# LB_BIT_w11_wirelessReceiver_v03_3_3_OHW.net
KiCad netlist of a schematic drawn in EAGLE
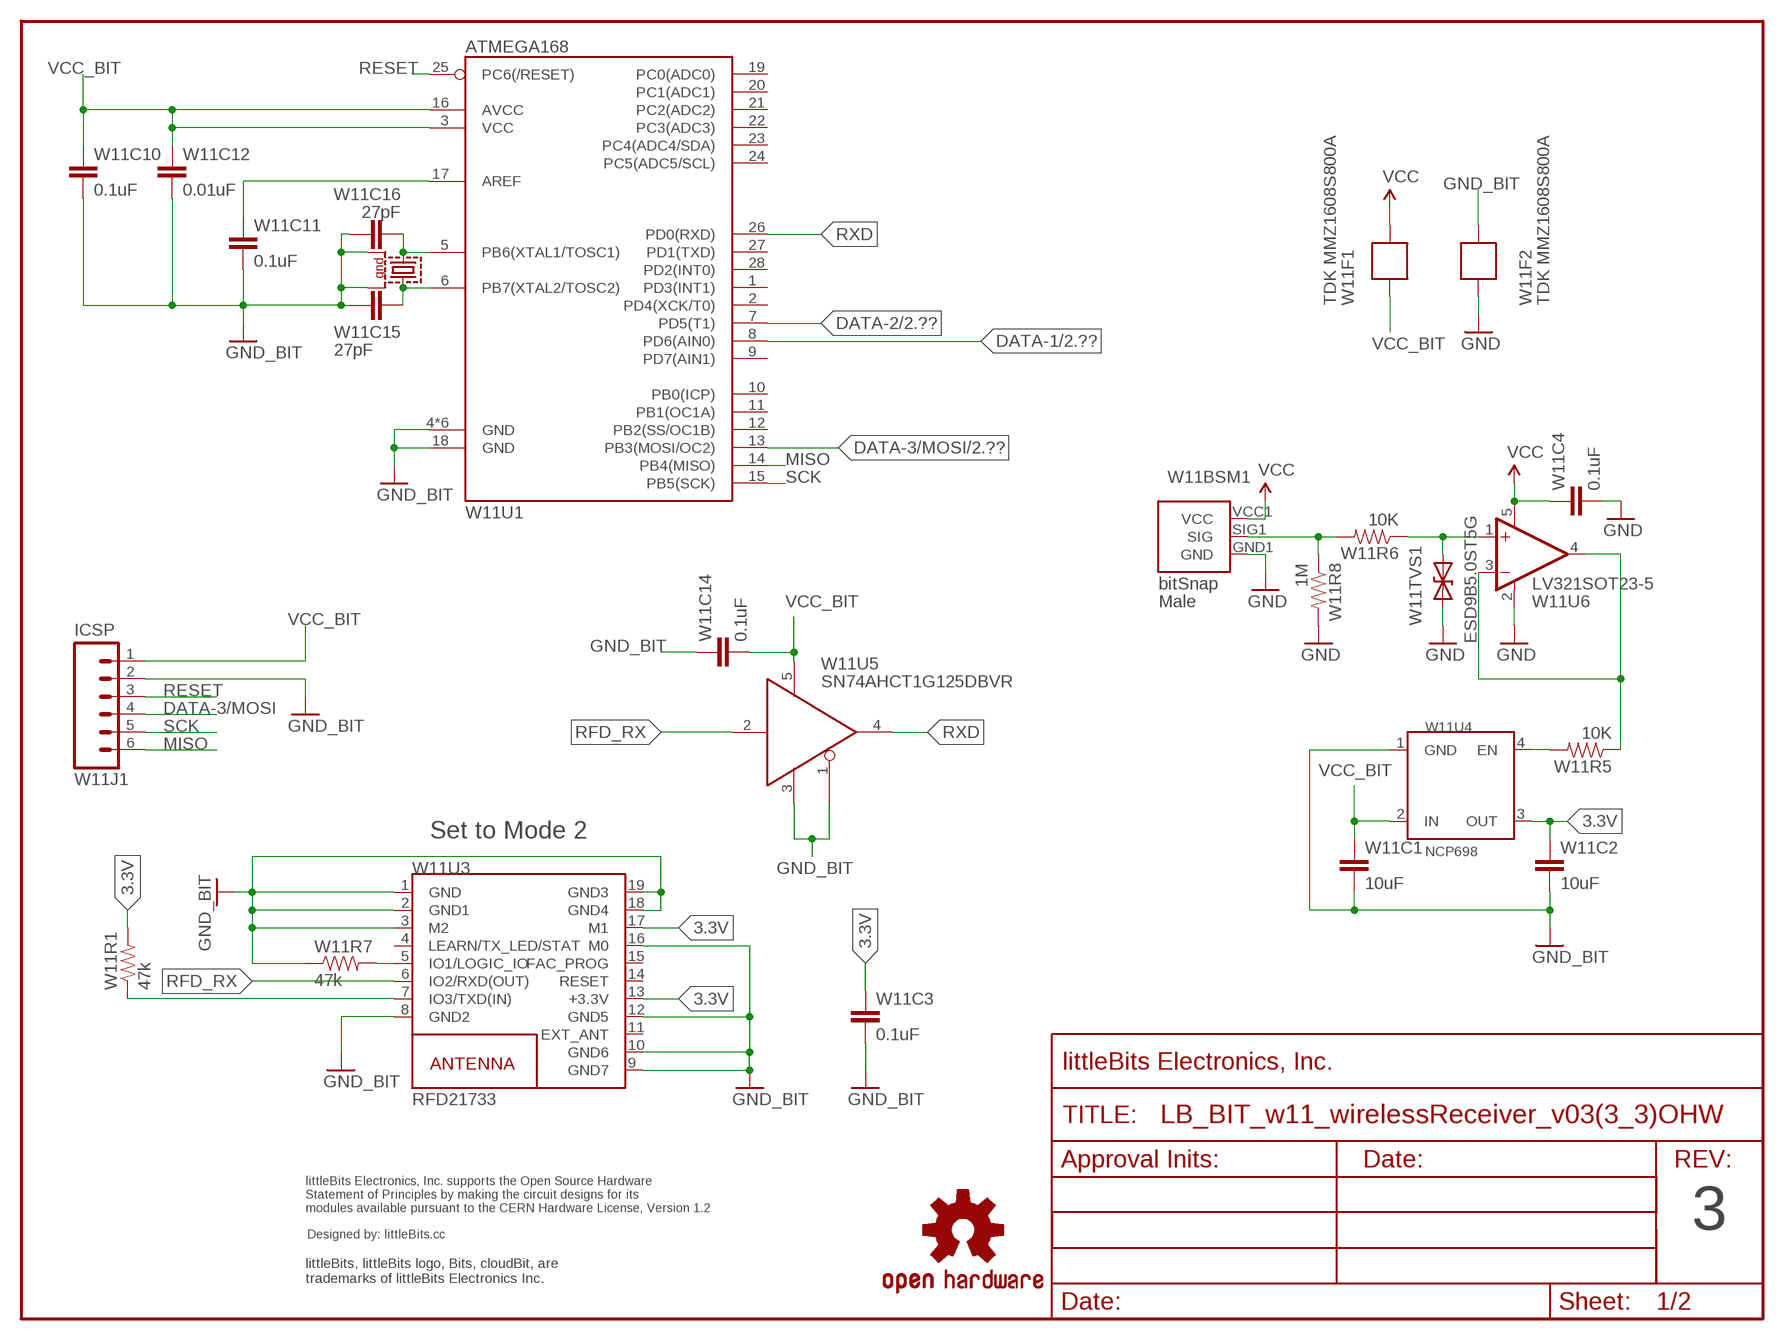
[diagram p0: schematic, sheet 1]
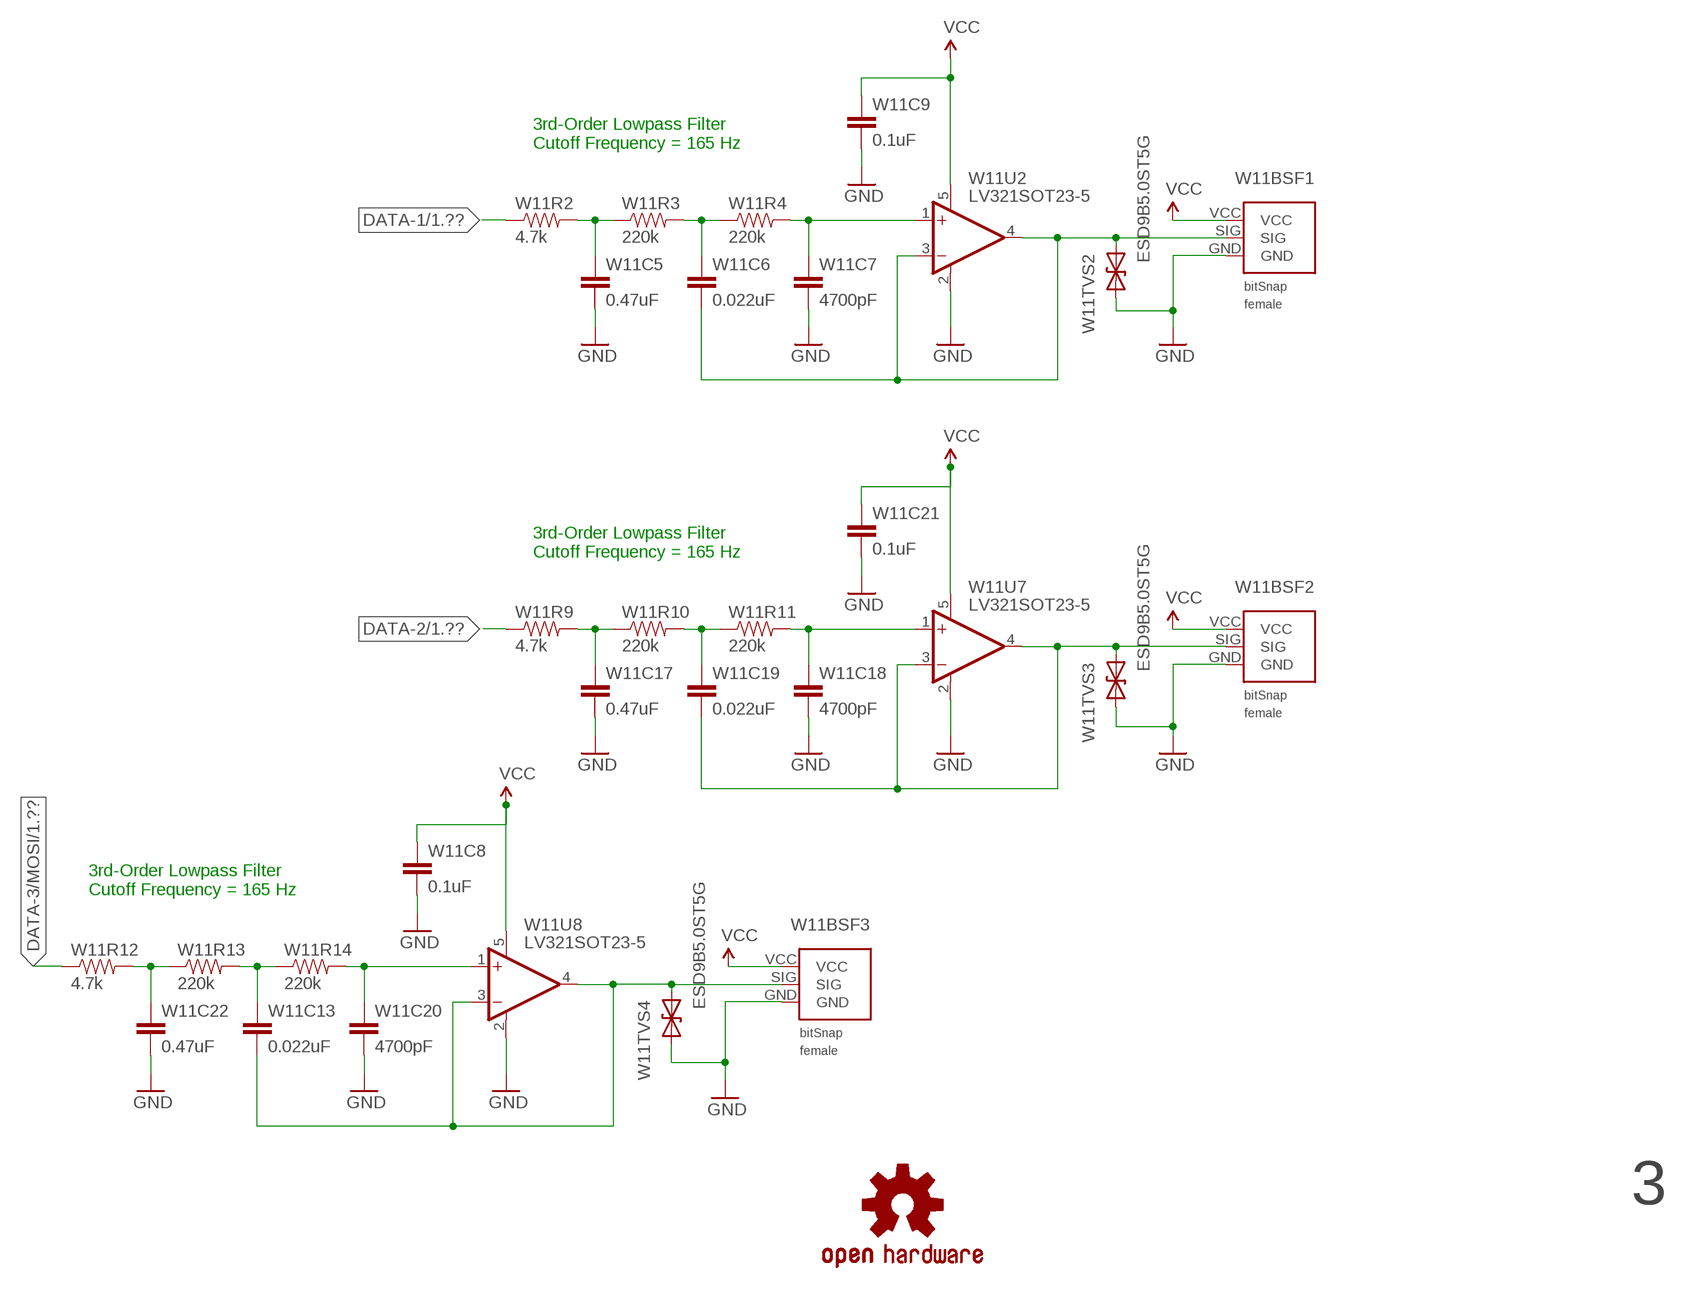
[diagram p1: schematic, sheet 2]

(export (version "E")
  (design (tool "Eeschema 10.0.6"))
  (components
    (comp (ref "FRAME1")
      (value "FRAME-LETTER-OHWOHW")
      (footprint "eagle-import:FABDWG01-OHW")
      (libsource (lib "eagle-import") (part "FRAME-LETTER-OHWOHW"))
    )
    (comp (ref "U$3")
      (value "OSHW-LOGOL")
      (footprint "eagle-import:OSHW-LOGO-L")
      (libsource (lib "eagle-import") (part "OSHW-LOGOL"))
    )
    (comp (ref "U$7")
      (value "OSHWCREDIT")
      (footprint "eagle-import:OSHWCREDIT")
      (libsource (lib "eagle-import") (part "OSHWCREDIT"))
    )
    (comp (ref "W11BSM1")
      (value "BITSNAP_V03_MALE")
      (footprint "eagle-import:BITSNAP_V03_MALE")
      (libsource (lib "eagle-import") (part "BITSNAP_V03_MALE"))
    )
    (comp (ref "W11C1")
      (value "10uF")
      (footprint "eagle-import:CAP-0603")
      (libsource (lib "eagle-import") (part "CAPCAP-0603"))
    )
    (comp (ref "W11C2")
      (value "10uF")
      (footprint "eagle-import:CAP-0603")
      (libsource (lib "eagle-import") (part "CAPCAP-0603"))
    )
    (comp (ref "W11C3")
      (value "0.1uF")
      (footprint "eagle-import:CAP-0603")
      (libsource (lib "eagle-import") (part "CAPCAP-0603"))
    )
    (comp (ref "W11C4")
      (value "0.1uF")
      (footprint "eagle-import:CAP-0603")
      (libsource (lib "eagle-import") (part "CAPCAP-0603"))
    )
    (comp (ref "W11C10")
      (value "0.1uF")
      (footprint "eagle-import:CAP-0603")
      (libsource (lib "eagle-import") (part "CAPCAP-0603"))
    )
    (comp (ref "W11C11")
      (value "0.1uF")
      (footprint "eagle-import:CAP-0603")
      (libsource (lib "eagle-import") (part "CAPCAP-0603"))
    )
    (comp (ref "W11C12")
      (value "0.01uF")
      (footprint "eagle-import:CAP-0603")
      (libsource (lib "eagle-import") (part "CAPCAP-0603"))
    )
    (comp (ref "W11C14")
      (value "0.1uF")
      (footprint "eagle-import:CAP-0603")
      (libsource (lib "eagle-import") (part "CAPCAP-0603"))
    )
    (comp (ref "W11C15")
      (value "27pF")
      (footprint "eagle-import:CAP-0603")
      (libsource (lib "eagle-import") (part "CAPCAP-0603"))
    )
    (comp (ref "W11C16")
      (value "27pF")
      (footprint "eagle-import:CAP-0603")
      (libsource (lib "eagle-import") (part "CAPCAP-0603"))
    )
    (comp (ref "W11F1")
      (value "TDK MMZ1608S800A")
      (footprint "eagle-import:R0603")
      (libsource (lib "eagle-import") (part "FERRITE-BEAD"))
    )
    (comp (ref "W11F2")
      (value "TDK MMZ1608S800A")
      (footprint "eagle-import:R0603")
      (libsource (lib "eagle-import") (part "FERRITE-BEAD"))
    )
    (comp (ref "W11J1")
      (value "ICSP")
      (footprint "eagle-import:SIP6-SM-0.1IN-NOS.S.")
      (libsource (lib "eagle-import") (part "HRD-60.1INCH_NO_SILKSCREEN"))
    )
    (comp (ref "W11R1")
      (value "47k")
      (footprint "eagle-import:RES-0603")
      (libsource (lib "eagle-import") (part "RESISTOR0603"))
    )
    (comp (ref "W11R5")
      (value "10K")
      (footprint "eagle-import:RES-0603")
      (libsource (lib "eagle-import") (part "RESISTOR0603"))
    )
    (comp (ref "W11R6")
      (value "10K")
      (footprint "eagle-import:RES-0603")
      (libsource (lib "eagle-import") (part "RESISTOR0603"))
    )
    (comp (ref "W11R7")
      (value "47k")
      (footprint "eagle-import:RES-0603")
      (libsource (lib "eagle-import") (part "RESISTOR0603"))
    )
    (comp (ref "W11R8")
      (value "1M")
      (footprint "eagle-import:RES-0603")
      (libsource (lib "eagle-import") (part "RESISTOR0603"))
    )
    (comp (ref "W11TVS1")
      (value "ESD9B5.0ST5G")
      (footprint "eagle-import:SOD-923")
      (libsource (lib "eagle-import") (part "DIODE-TVSSOD-923"))
    )
    (comp (ref "W11U1")
      (value "ATMEGA168")
      (footprint "eagle-import:VQFN28")
      (libsource (lib "eagle-import") (part "ATMEGA168-28PINVFQFN-28"))
    )
    (comp (ref "W11U3")
      (value "RFD21733")
      (footprint "eagle-import:RFD21733")
      (libsource (lib "eagle-import") (part "RFD_CHIP"))
    )
    (comp (ref "W11U4")
      (value "NCP698")
      (footprint "eagle-import:NCP698_SC82-AB")
      (libsource (lib "eagle-import") (part "NCP698"))
    )
    (comp (ref "W11U5")
      (value "SN74AHCT1G125DBVR")
      (footprint "eagle-import:SOT23-5")
      (libsource (lib "eagle-import") (part "5V_TO_3.3V_LEVEL-SHIFTERSOT23-5"))
    )
    (comp (ref "W11U6")
      (value "LV321SOT23-5")
      (footprint "eagle-import:SOT23-5")
      (libsource (lib "eagle-import") (part "LV321SOT23-5"))
    )
    (comp (ref "W11X1")
      (value "7B-8.000MAAJ-T")
      (footprint "eagle-import:CRYSTAL-SMD-7B-SERIES-5X3.2MM")
      (fields (field (name "MFG") "TXC") (field (name "MPN") "7B SERIES"))
      (libsource (lib "eagle-import") (part "CRYSTAL-SMD-7B-SERIES-TXC"))
    )
    (comp (ref "U$9")
      (value "OSHW-LOGOL")
      (footprint "eagle-import:OSHW-LOGO-L")
      (libsource (lib "eagle-import") (part "OSHW-LOGOL"))
    )
    (comp (ref "W11BSF1")
      (value "BITSNAP_V03_FEMALE")
      (footprint "eagle-import:BITSNAP_V03_FEMALE")
      (libsource (lib "eagle-import") (part "BITSNAP_V03_FEMALE"))
    )
    (comp (ref "W11BSF2")
      (value "BITSNAP_V03_FEMALE")
      (footprint "eagle-import:BITSNAP_V03_FEMALE")
      (libsource (lib "eagle-import") (part "BITSNAP_V03_FEMALE"))
    )
    (comp (ref "W11BSF3")
      (value "BITSNAP_V03_FEMALE")
      (footprint "eagle-import:BITSNAP_V03_FEMALE")
      (libsource (lib "eagle-import") (part "BITSNAP_V03_FEMALE"))
    )
    (comp (ref "W11C5")
      (value "0.47uF")
      (footprint "eagle-import:CAP-0603")
      (libsource (lib "eagle-import") (part "CAPCAP-0603"))
    )
    (comp (ref "W11C6")
      (value "0.022uF")
      (footprint "eagle-import:CAP-0603")
      (libsource (lib "eagle-import") (part "CAPCAP-0603"))
    )
    (comp (ref "W11C7")
      (value "4700pF")
      (footprint "eagle-import:CAP-0603")
      (libsource (lib "eagle-import") (part "CAPCAP-0603"))
    )
    (comp (ref "W11C8")
      (value "0.1uF")
      (footprint "eagle-import:CAP-0603")
      (libsource (lib "eagle-import") (part "CAPCAP-0603"))
    )
    (comp (ref "W11C9")
      (value "0.1uF")
      (footprint "eagle-import:CAP-0603")
      (libsource (lib "eagle-import") (part "CAPCAP-0603"))
    )
    (comp (ref "W11C13")
      (value "0.022uF")
      (footprint "eagle-import:CAP-0603")
      (libsource (lib "eagle-import") (part "CAPCAP-0603"))
    )
    (comp (ref "W11C17")
      (value "0.47uF")
      (footprint "eagle-import:CAP-0603")
      (libsource (lib "eagle-import") (part "CAPCAP-0603"))
    )
    (comp (ref "W11C18")
      (value "4700pF")
      (footprint "eagle-import:CAP-0603")
      (libsource (lib "eagle-import") (part "CAPCAP-0603"))
    )
    (comp (ref "W11C19")
      (value "0.022uF")
      (footprint "eagle-import:CAP-0603")
      (libsource (lib "eagle-import") (part "CAPCAP-0603"))
    )
    (comp (ref "W11C20")
      (value "4700pF")
      (footprint "eagle-import:CAP-0603")
      (libsource (lib "eagle-import") (part "CAPCAP-0603"))
    )
    (comp (ref "W11C21")
      (value "0.1uF")
      (footprint "eagle-import:CAP-0603")
      (libsource (lib "eagle-import") (part "CAPCAP-0603"))
    )
    (comp (ref "W11C22")
      (value "0.47uF")
      (footprint "eagle-import:CAP-0603")
      (libsource (lib "eagle-import") (part "CAPCAP-0603"))
    )
    (comp (ref "W11R2")
      (value "4.7k")
      (footprint "eagle-import:RES-0603")
      (libsource (lib "eagle-import") (part "RESISTOR0603"))
    )
    (comp (ref "W11R3")
      (value "220k")
      (footprint "eagle-import:RES-0603")
      (libsource (lib "eagle-import") (part "RESISTOR0603"))
    )
    (comp (ref "W11R4")
      (value "220k")
      (footprint "eagle-import:RES-0603")
      (libsource (lib "eagle-import") (part "RESISTOR0603"))
    )
    (comp (ref "W11R9")
      (value "4.7k")
      (footprint "eagle-import:RES-0603")
      (libsource (lib "eagle-import") (part "RESISTOR0603"))
    )
    (comp (ref "W11R10")
      (value "220k")
      (footprint "eagle-import:RES-0603")
      (libsource (lib "eagle-import") (part "RESISTOR0603"))
    )
    (comp (ref "W11R11")
      (value "220k")
      (footprint "eagle-import:RES-0603")
      (libsource (lib "eagle-import") (part "RESISTOR0603"))
    )
    (comp (ref "W11R12")
      (value "4.7k")
      (footprint "eagle-import:RES-0603")
      (libsource (lib "eagle-import") (part "RESISTOR0603"))
    )
    (comp (ref "W11R13")
      (value "220k")
      (footprint "eagle-import:RES-0603")
      (libsource (lib "eagle-import") (part "RESISTOR0603"))
    )
    (comp (ref "W11R14")
      (value "220k")
      (footprint "eagle-import:RES-0603")
      (libsource (lib "eagle-import") (part "RESISTOR0603"))
    )
    (comp (ref "W11TVS2")
      (value "ESD9B5.0ST5G")
      (footprint "eagle-import:SOD-923")
      (libsource (lib "eagle-import") (part "DIODE-TVSSOD-923"))
    )
    (comp (ref "W11TVS3")
      (value "ESD9B5.0ST5G")
      (footprint "eagle-import:SOD-923")
      (libsource (lib "eagle-import") (part "DIODE-TVSSOD-923"))
    )
    (comp (ref "W11TVS4")
      (value "ESD9B5.0ST5G")
      (footprint "eagle-import:SOD-923")
      (libsource (lib "eagle-import") (part "DIODE-TVSSOD-923"))
    )
    (comp (ref "W11U2")
      (value "LV321SOT23-5")
      (footprint "eagle-import:SOT23-5")
      (libsource (lib "eagle-import") (part "LV321SOT23-5"))
    )
    (comp (ref "W11U7")
      (value "LV321SOT23-5")
      (footprint "eagle-import:SOT23-5")
      (libsource (lib "eagle-import") (part "LV321SOT23-5"))
    )
    (comp (ref "W11U8")
      (value "LV321SOT23-5")
      (footprint "eagle-import:SOT23-5")
      (libsource (lib "eagle-import") (part "LV321SOT23-5"))
    )
  )
  (nets
    (net (code "1") (name "3.3V") (class "Default")
      (node (ref "W11C2") (pin "1") (pinfunction "1_1") (pintype "passive"))
      (node (ref "W11C3") (pin "1") (pinfunction "1_1") (pintype "passive"))
      (node (ref "W11R1") (pin "2") (pinfunction "2_2") (pintype "passive"))
      (node (ref "W11U3") (pin "13") (pinfunction "+3.3V_13") (pintype "bidirectional"))
      (node (ref "W11U3") (pin "17") (pinfunction "M1_17") (pintype "bidirectional"))
      (node (ref "W11U4") (pin "3") (pinfunction "OUT_3") (pintype "bidirectional"))
    )
    (net (code "2") (name "DATA-1") (class "Default")
      (node (ref "W11R2") (pin "1") (pinfunction "1_1") (pintype "passive"))
      (node (ref "W11U1") (pin "8") (pinfunction "PD6(AIN0)_8") (pintype "bidirectional"))
    )
    (net (code "3") (name "DATA-2") (class "Default")
      (node (ref "W11R9") (pin "1") (pinfunction "1_1") (pintype "passive"))
      (node (ref "W11U1") (pin "7") (pinfunction "PD5(T1)_7") (pintype "bidirectional"))
    )
    (net (code "4") (name "DATA-3{slash}MOSI") (class "Default")
      (node (ref "W11J1") (pin "4") (pinfunction "4_4") (pintype "passive"))
      (node (ref "W11R12") (pin "1") (pinfunction "1_1") (pintype "passive"))
      (node (ref "W11U1") (pin "13") (pinfunction "PB3(MOSI/OC2)_13") (pintype "bidirectional"))
    )
    (net (code "5") (name "GND") (class "Default")
      (node (ref "W11BSF1") (pin "GND") (pinfunction "GND_GND") (pintype "bidirectional"))
      (node (ref "W11BSF2") (pin "GND") (pinfunction "GND_GND") (pintype "bidirectional"))
      (node (ref "W11BSF3") (pin "GND") (pinfunction "GND_GND") (pintype "bidirectional"))
      (node (ref "W11BSM1") (pin "GND1") (pinfunction "GND_GND1") (pintype "bidirectional"))
      (node (ref "W11C17") (pin "2") (pinfunction "2_2") (pintype "passive"))
      (node (ref "W11C18") (pin "2") (pinfunction "2_2") (pintype "passive"))
      (node (ref "W11C20") (pin "2") (pinfunction "2_2") (pintype "passive"))
      (node (ref "W11C21") (pin "2") (pinfunction "2_2") (pintype "passive"))
      (node (ref "W11C22") (pin "2") (pinfunction "2_2") (pintype "passive"))
      (node (ref "W11C4") (pin "2") (pinfunction "2_2") (pintype "passive"))
      (node (ref "W11C5") (pin "2") (pinfunction "2_2") (pintype "passive"))
      (node (ref "W11C7") (pin "2") (pinfunction "2_2") (pintype "passive"))
      (node (ref "W11C8") (pin "2") (pinfunction "2_2") (pintype "passive"))
      (node (ref "W11C9") (pin "2") (pinfunction "2_2") (pintype "passive"))
      (node (ref "W11F2") (pin "2") (pinfunction "P$2_2") (pintype "bidirectional"))
      (node (ref "W11R8") (pin "2") (pinfunction "2_2") (pintype "passive"))
      (node (ref "W11TVS1") (pin "1") (pinfunction "A_1") (pintype "passive"))
      (node (ref "W11TVS2") (pin "1") (pinfunction "A_1") (pintype "passive"))
      (node (ref "W11TVS3") (pin "1") (pinfunction "A_1") (pintype "passive"))
      (node (ref "W11TVS4") (pin "1") (pinfunction "A_1") (pintype "passive"))
      (node (ref "W11U2") (pin "2") (pinfunction "V-_2") (pintype "power_in"))
      (node (ref "W11U6") (pin "2") (pinfunction "V-_2") (pintype "power_in"))
      (node (ref "W11U7") (pin "2") (pinfunction "V-_2") (pintype "power_in"))
      (node (ref "W11U8") (pin "2") (pinfunction "V-_2") (pintype "power_in"))
    )
    (net (code "6") (name "GND_BIT") (class "Default")
      (node (ref "W11C1") (pin "2") (pinfunction "2_2") (pintype "passive"))
      (node (ref "W11C10") (pin "2") (pinfunction "2_2") (pintype "passive"))
      (node (ref "W11C11") (pin "2") (pinfunction "2_2") (pintype "passive"))
      (node (ref "W11C12") (pin "2") (pinfunction "2_2") (pintype "passive"))
      (node (ref "W11C14") (pin "1") (pinfunction "1_1") (pintype "passive"))
      (node (ref "W11C15") (pin "2") (pinfunction "2_2") (pintype "passive"))
      (node (ref "W11C16") (pin "1") (pinfunction "1_1") (pintype "passive"))
      (node (ref "W11C2") (pin "2") (pinfunction "2_2") (pintype "passive"))
      (node (ref "W11C3") (pin "2") (pinfunction "2_2") (pintype "passive"))
      (node (ref "W11F2") (pin "1") (pinfunction "P$1_1") (pintype "bidirectional"))
      (node (ref "W11J1") (pin "2") (pinfunction "2_2") (pintype "passive"))
      (node (ref "W11R7") (pin "1") (pinfunction "1_1") (pintype "passive"))
      (node (ref "W11U1") (pin "18") (pinfunction "GND_18") (pintype "bidirectional"))
      (node (ref "W11U1") (pin "4") (pinfunction "GND_4") (pintype "bidirectional"))
      (node (ref "W11U1") (pin "TH") (pinfunction "GND_TH") (pintype "bidirectional"))
      (node (ref "W11U1") (pin "TH@1") (pinfunction "GND_TH@1") (pintype "bidirectional"))
      (node (ref "W11U1") (pin "TH@2") (pinfunction "GND_TH@2") (pintype "bidirectional"))
      (node (ref "W11U1") (pin "TH@3") (pinfunction "GND_TH@3") (pintype "bidirectional"))
      (node (ref "W11U1") (pin "TH@4") (pinfunction "GND_TH@4") (pintype "bidirectional"))
      (node (ref "W11U3") (pin "1") (pinfunction "GND_1") (pintype "bidirectional"))
      (node (ref "W11U3") (pin "10") (pinfunction "GND6_10") (pintype "bidirectional"))
      (node (ref "W11U3") (pin "12") (pinfunction "GND5_12") (pintype "bidirectional"))
      (node (ref "W11U3") (pin "16") (pinfunction "M0_16") (pintype "bidirectional"))
      (node (ref "W11U3") (pin "18") (pinfunction "GND4_18") (pintype "bidirectional"))
      (node (ref "W11U3") (pin "19") (pinfunction "GND3_19") (pintype "bidirectional"))
      (node (ref "W11U3") (pin "2") (pinfunction "GND1_2") (pintype "bidirectional"))
      (node (ref "W11U3") (pin "3") (pinfunction "M2_3") (pintype "bidirectional"))
      (node (ref "W11U3") (pin "8") (pinfunction "GND2_8") (pintype "bidirectional"))
      (node (ref "W11U3") (pin "9") (pinfunction "GND7_9") (pintype "bidirectional"))
      (node (ref "W11U4") (pin "1") (pinfunction "GND_1") (pintype "bidirectional"))
      (node (ref "W11U5") (pin "1") (pinfunction "1_1") (pintype "bidirectional"))
      (node (ref "W11U5") (pin "3") (pinfunction "3_3") (pintype "bidirectional"))
      (node (ref "W11X1") (pin "P$2") (pinfunction "2_P$2") (pintype "passive"))
      (node (ref "W11X1") (pin "P$4") (pinfunction "4_P$4") (pintype "passive"))
    )
    (net (code "7") (name "MISO") (class "Default")
      (node (ref "W11J1") (pin "6") (pinfunction "6_6") (pintype "passive"))
      (node (ref "W11U1") (pin "14") (pinfunction "PB4(MISO)_14") (pintype "bidirectional"))
    )
    (net (code "8") (name "Net-(W11BSM1-SIG)") (class "Default")
      (node (ref "W11BSM1") (pin "SIG1") (pinfunction "SIG_SIG1") (pintype "bidirectional"))
      (node (ref "W11R6") (pin "2") (pinfunction "2_2") (pintype "passive"))
      (node (ref "W11R8") (pin "1") (pinfunction "1_1") (pintype "passive"))
    )
    (net (code "9") (name "Net-(W11C5-Pad1)") (class "Default")
      (node (ref "W11C5") (pin "1") (pinfunction "1_1") (pintype "passive"))
      (node (ref "W11R2") (pin "2") (pinfunction "2_2") (pintype "passive"))
      (node (ref "W11R3") (pin "1") (pinfunction "1_1") (pintype "passive"))
    )
    (net (code "10") (name "Net-(W11C6-Pad1)") (class "Default")
      (node (ref "W11C6") (pin "1") (pinfunction "1_1") (pintype "passive"))
      (node (ref "W11R3") (pin "2") (pinfunction "2_2") (pintype "passive"))
      (node (ref "W11R4") (pin "1") (pinfunction "1_1") (pintype "passive"))
    )
    (net (code "11") (name "Net-(W11C13-Pad1)") (class "Default")
      (node (ref "W11C13") (pin "1") (pinfunction "1_1") (pintype "passive"))
      (node (ref "W11R13") (pin "2") (pinfunction "2_2") (pintype "passive"))
      (node (ref "W11R14") (pin "1") (pinfunction "1_1") (pintype "passive"))
    )
    (net (code "12") (name "Net-(W11C17-Pad1)") (class "Default")
      (node (ref "W11C17") (pin "1") (pinfunction "1_1") (pintype "passive"))
      (node (ref "W11R10") (pin "1") (pinfunction "1_1") (pintype "passive"))
      (node (ref "W11R9") (pin "2") (pinfunction "2_2") (pintype "passive"))
    )
    (net (code "13") (name "Net-(W11C19-Pad1)") (class "Default")
      (node (ref "W11C19") (pin "1") (pinfunction "1_1") (pintype "passive"))
      (node (ref "W11R10") (pin "2") (pinfunction "2_2") (pintype "passive"))
      (node (ref "W11R11") (pin "1") (pinfunction "1_1") (pintype "passive"))
    )
    (net (code "14") (name "Net-(W11C22-Pad1)") (class "Default")
      (node (ref "W11C22") (pin "1") (pinfunction "1_1") (pintype "passive"))
      (node (ref "W11R12") (pin "2") (pinfunction "2_2") (pintype "passive"))
      (node (ref "W11R13") (pin "1") (pinfunction "1_1") (pintype "passive"))
    )
    (net (code "15") (name "Net-(W11TVS1-C)") (class "Default")
      (node (ref "W11R6") (pin "1") (pinfunction "1_1") (pintype "passive"))
      (node (ref "W11TVS1") (pin "2") (pinfunction "C_2") (pintype "passive"))
      (node (ref "W11U6") (pin "1") (pinfunction "+IN_1") (pintype "input"))
    )
    (net (code "16") (name "Net-(W11TVS2-C)") (class "Default")
      (node (ref "W11BSF1") (pin "SIG") (pinfunction "SIG_SIG") (pintype "bidirectional"))
      (node (ref "W11C6") (pin "2") (pinfunction "2_2") (pintype "passive"))
      (node (ref "W11TVS2") (pin "2") (pinfunction "C_2") (pintype "passive"))
      (node (ref "W11U2") (pin "3") (pinfunction "-IN_3") (pintype "input"))
      (node (ref "W11U2") (pin "4") (pinfunction "OUT_4") (pintype "output"))
    )
    (net (code "17") (name "Net-(W11TVS3-C)") (class "Default")
      (node (ref "W11BSF2") (pin "SIG") (pinfunction "SIG_SIG") (pintype "bidirectional"))
      (node (ref "W11C19") (pin "2") (pinfunction "2_2") (pintype "passive"))
      (node (ref "W11TVS3") (pin "2") (pinfunction "C_2") (pintype "passive"))
      (node (ref "W11U7") (pin "3") (pinfunction "-IN_3") (pintype "input"))
      (node (ref "W11U7") (pin "4") (pinfunction "OUT_4") (pintype "output"))
    )
    (net (code "18") (name "Net-(W11TVS4-C)") (class "Default")
      (node (ref "W11BSF3") (pin "SIG") (pinfunction "SIG_SIG") (pintype "bidirectional"))
      (node (ref "W11C13") (pin "2") (pinfunction "2_2") (pintype "passive"))
      (node (ref "W11TVS4") (pin "2") (pinfunction "C_2") (pintype "passive"))
      (node (ref "W11U8") (pin "3") (pinfunction "-IN_3") (pintype "input"))
      (node (ref "W11U8") (pin "4") (pinfunction "OUT_4") (pintype "output"))
    )
    (net (code "19") (name "Net-(W11U1-AREF)") (class "Default")
      (node (ref "W11C11") (pin "1") (pinfunction "1_1") (pintype "passive"))
      (node (ref "W11U1") (pin "17") (pinfunction "AREF_17") (pintype "bidirectional"))
    )
    (net (code "20") (name "Net-(W11U1-PB6(XTAL1{slash}TOSC1))") (class "Default")
      (node (ref "W11C16") (pin "2") (pinfunction "2_2") (pintype "passive"))
      (node (ref "W11U1") (pin "5") (pinfunction "PB6(XTAL1/TOSC1)_5") (pintype "bidirectional"))
      (node (ref "W11X1") (pin "P$1") (pinfunction "1_P$1") (pintype "passive"))
    )
    (net (code "21") (name "Net-(W11U1-PB7(XTAL2{slash}TOSC2))") (class "Default")
      (node (ref "W11C15") (pin "1") (pinfunction "1_1") (pintype "passive"))
      (node (ref "W11U1") (pin "6") (pinfunction "PB7(XTAL2/TOSC2)_6") (pintype "bidirectional"))
      (node (ref "W11X1") (pin "P$3") (pinfunction "3_P$3") (pintype "passive"))
    )
    (net (code "22") (name "Net-(W11U2-+IN)") (class "Default")
      (node (ref "W11C7") (pin "1") (pinfunction "1_1") (pintype "passive"))
      (node (ref "W11R4") (pin "2") (pinfunction "2_2") (pintype "passive"))
      (node (ref "W11U2") (pin "1") (pinfunction "+IN_1") (pintype "input"))
    )
    (net (code "23") (name "Net-(W11U3-IO1{slash}LOGIC_IO)") (class "Default")
      (node (ref "W11R7") (pin "2") (pinfunction "2_2") (pintype "passive"))
      (node (ref "W11U3") (pin "5") (pinfunction "IO1/LOGIC_IO_5") (pintype "bidirectional"))
    )
    (net (code "24") (name "Net-(W11U3-IO3{slash}TXD(IN))") (class "Default")
      (node (ref "W11R1") (pin "1") (pinfunction "1_1") (pintype "passive"))
      (node (ref "W11U3") (pin "7") (pinfunction "IO3/TXD(IN)_7") (pintype "bidirectional"))
    )
    (net (code "25") (name "Net-(W11U4-EN)") (class "Default")
      (node (ref "W11R5") (pin "2") (pinfunction "2_2") (pintype "passive"))
      (node (ref "W11U4") (pin "4") (pinfunction "EN_4") (pintype "bidirectional"))
    )
    (net (code "26") (name "Net-(W11U6--IN)") (class "Default")
      (node (ref "W11R5") (pin "1") (pinfunction "1_1") (pintype "passive"))
      (node (ref "W11U6") (pin "3") (pinfunction "-IN_3") (pintype "input"))
      (node (ref "W11U6") (pin "4") (pinfunction "OUT_4") (pintype "output"))
    )
    (net (code "27") (name "Net-(W11U7-+IN)") (class "Default")
      (node (ref "W11C18") (pin "1") (pinfunction "1_1") (pintype "passive"))
      (node (ref "W11R11") (pin "2") (pinfunction "2_2") (pintype "passive"))
      (node (ref "W11U7") (pin "1") (pinfunction "+IN_1") (pintype "input"))
    )
    (net (code "28") (name "Net-(W11U8-+IN)") (class "Default")
      (node (ref "W11C20") (pin "1") (pinfunction "1_1") (pintype "passive"))
      (node (ref "W11R14") (pin "2") (pinfunction "2_2") (pintype "passive"))
      (node (ref "W11U8") (pin "1") (pinfunction "+IN_1") (pintype "input"))
    )
    (net (code "29") (name "RESET") (class "Default")
      (node (ref "W11J1") (pin "3") (pinfunction "3_3") (pintype "passive"))
      (node (ref "W11U1") (pin "25") (pinfunction "PC6(/RESET)_25") (pintype "bidirectional"))
    )
    (net (code "30") (name "RFD_RX") (class "Default")
      (node (ref "W11U3") (pin "6") (pinfunction "IO2/RXD(OUT)_6") (pintype "bidirectional"))
      (node (ref "W11U5") (pin "2") (pinfunction "2_2") (pintype "bidirectional"))
    )
    (net (code "31") (name "RXD") (class "Default")
      (node (ref "W11U1") (pin "26") (pinfunction "PD0(RXD)_26") (pintype "bidirectional"))
      (node (ref "W11U5") (pin "4") (pinfunction "4_4") (pintype "bidirectional"))
    )
    (net (code "32") (name "SCK") (class "Default")
      (node (ref "W11J1") (pin "5") (pinfunction "5_5") (pintype "passive"))
      (node (ref "W11U1") (pin "15") (pinfunction "PB5(SCK)_15") (pintype "bidirectional"))
    )
    (net (code "33") (name "VCC") (class "Default")
      (node (ref "W11BSF1") (pin "VCC") (pinfunction "VCC_VCC") (pintype "bidirectional"))
      (node (ref "W11BSF2") (pin "VCC") (pinfunction "VCC_VCC") (pintype "bidirectional"))
      (node (ref "W11BSF3") (pin "VCC") (pinfunction "VCC_VCC") (pintype "bidirectional"))
      (node (ref "W11BSM1") (pin "VCC1") (pinfunction "VCC_VCC1") (pintype "bidirectional"))
      (node (ref "W11C21") (pin "1") (pinfunction "1_1") (pintype "passive"))
      (node (ref "W11C4") (pin "1") (pinfunction "1_1") (pintype "passive"))
      (node (ref "W11C8") (pin "1") (pinfunction "1_1") (pintype "passive"))
      (node (ref "W11C9") (pin "1") (pinfunction "1_1") (pintype "passive"))
      (node (ref "W11F1") (pin "1") (pinfunction "P$1_1") (pintype "bidirectional"))
      (node (ref "W11U2") (pin "5") (pinfunction "V+_5") (pintype "power_in"))
      (node (ref "W11U6") (pin "5") (pinfunction "V+_5") (pintype "power_in"))
      (node (ref "W11U7") (pin "5") (pinfunction "V+_5") (pintype "power_in"))
      (node (ref "W11U8") (pin "5") (pinfunction "V+_5") (pintype "power_in"))
    )
    (net (code "34") (name "VCC_BIT") (class "Default")
      (node (ref "W11C1") (pin "1") (pinfunction "1_1") (pintype "passive"))
      (node (ref "W11C10") (pin "1") (pinfunction "1_1") (pintype "passive"))
      (node (ref "W11C12") (pin "1") (pinfunction "1_1") (pintype "passive"))
      (node (ref "W11C14") (pin "2") (pinfunction "2_2") (pintype "passive"))
      (node (ref "W11F1") (pin "2") (pinfunction "P$2_2") (pintype "bidirectional"))
      (node (ref "W11J1") (pin "1") (pinfunction "1_1") (pintype "passive"))
      (node (ref "W11U1") (pin "16") (pinfunction "AVCC_16") (pintype "bidirectional"))
      (node (ref "W11U1") (pin "3") (pinfunction "VCC_3") (pintype "bidirectional"))
      (node (ref "W11U4") (pin "2") (pinfunction "IN_2") (pintype "bidirectional"))
      (node (ref "W11U5") (pin "5") (pinfunction "5_5") (pintype "bidirectional"))
    )
    (net (code "35") (name "unconnected-(W11U1-PB0(ICP)-Pad10)") (class "Default")
      (node (ref "W11U1") (pin "10") (pinfunction "PB0(ICP)_10") (pintype "bidirectional"))
    )
    (net (code "36") (name "unconnected-(W11U1-PB1(OC1A)-Pad11)") (class "Default")
      (node (ref "W11U1") (pin "11") (pinfunction "PB1(OC1A)_11") (pintype "bidirectional"))
    )
    (net (code "37") (name "unconnected-(W11U1-PB2(SS{slash}OC1B)-Pad12)") (class "Default")
      (node (ref "W11U1") (pin "12") (pinfunction "PB2(SS/OC1B)_12") (pintype "bidirectional"))
    )
    (net (code "38") (name "unconnected-(W11U1-PC0(ADC0)-Pad19)") (class "Default")
      (node (ref "W11U1") (pin "19") (pinfunction "PC0(ADC0)_19") (pintype "bidirectional"))
    )
    (net (code "39") (name "unconnected-(W11U1-PC1(ADC1)-Pad20)") (class "Default")
      (node (ref "W11U1") (pin "20") (pinfunction "PC1(ADC1)_20") (pintype "bidirectional"))
    )
    (net (code "40") (name "unconnected-(W11U1-PC2(ADC2)-Pad21)") (class "Default")
      (node (ref "W11U1") (pin "21") (pinfunction "PC2(ADC2)_21") (pintype "bidirectional"))
    )
    (net (code "41") (name "unconnected-(W11U1-PC3(ADC3)-Pad22)") (class "Default")
      (node (ref "W11U1") (pin "22") (pinfunction "PC3(ADC3)_22") (pintype "bidirectional"))
    )
    (net (code "42") (name "unconnected-(W11U1-PC4(ADC4{slash}SDA)-Pad23)") (class "Default")
      (node (ref "W11U1") (pin "23") (pinfunction "PC4(ADC4/SDA)_23") (pintype "bidirectional"))
    )
    (net (code "43") (name "unconnected-(W11U1-PC5(ADC5{slash}SCL)-Pad24)") (class "Default")
      (node (ref "W11U1") (pin "24") (pinfunction "PC5(ADC5/SCL)_24") (pintype "bidirectional"))
    )
    (net (code "44") (name "unconnected-(W11U1-PD1(TXD)-Pad27)") (class "Default")
      (node (ref "W11U1") (pin "27") (pinfunction "PD1(TXD)_27") (pintype "bidirectional"))
    )
    (net (code "45") (name "unconnected-(W11U1-PD2(INT0)-Pad28)") (class "Default")
      (node (ref "W11U1") (pin "28") (pinfunction "PD2(INT0)_28") (pintype "bidirectional"))
    )
    (net (code "46") (name "unconnected-(W11U1-PD3(INT1)-Pad1)") (class "Default")
      (node (ref "W11U1") (pin "1") (pinfunction "PD3(INT1)_1") (pintype "bidirectional"))
    )
    (net (code "47") (name "unconnected-(W11U1-PD4(XCK{slash}T0)-Pad2)") (class "Default")
      (node (ref "W11U1") (pin "2") (pinfunction "PD4(XCK/T0)_2") (pintype "bidirectional"))
    )
    (net (code "48") (name "unconnected-(W11U1-PD7(AIN1)-Pad9)") (class "Default")
      (node (ref "W11U1") (pin "9") (pinfunction "PD7(AIN1)_9") (pintype "bidirectional"))
    )
    (net (code "49") (name "unconnected-(W11U3-EXT_ANT-Pad11)") (class "Default")
      (node (ref "W11U3") (pin "11") (pinfunction "EXT_ANT_11") (pintype "bidirectional"))
    )
    (net (code "50") (name "unconnected-(W11U3-FAC_PROG-Pad15)") (class "Default")
      (node (ref "W11U3") (pin "15") (pinfunction "FAC_PROG_15") (pintype "bidirectional"))
    )
    (net (code "51") (name "unconnected-(W11U3-LEARN{slash}TX_LED{slash}STAT-Pad4)") (class "Default")
      (node (ref "W11U3") (pin "4") (pinfunction "LEARN/TX_LED/STAT_4") (pintype "bidirectional"))
    )
    (net (code "52") (name "unconnected-(W11U3-RESET-Pad14)") (class "Default")
      (node (ref "W11U3") (pin "14") (pinfunction "RESET_14") (pintype "bidirectional"))
    )
  )
)
